# power_node.net
KiCad netlist of a schematic drawn in EAGLE
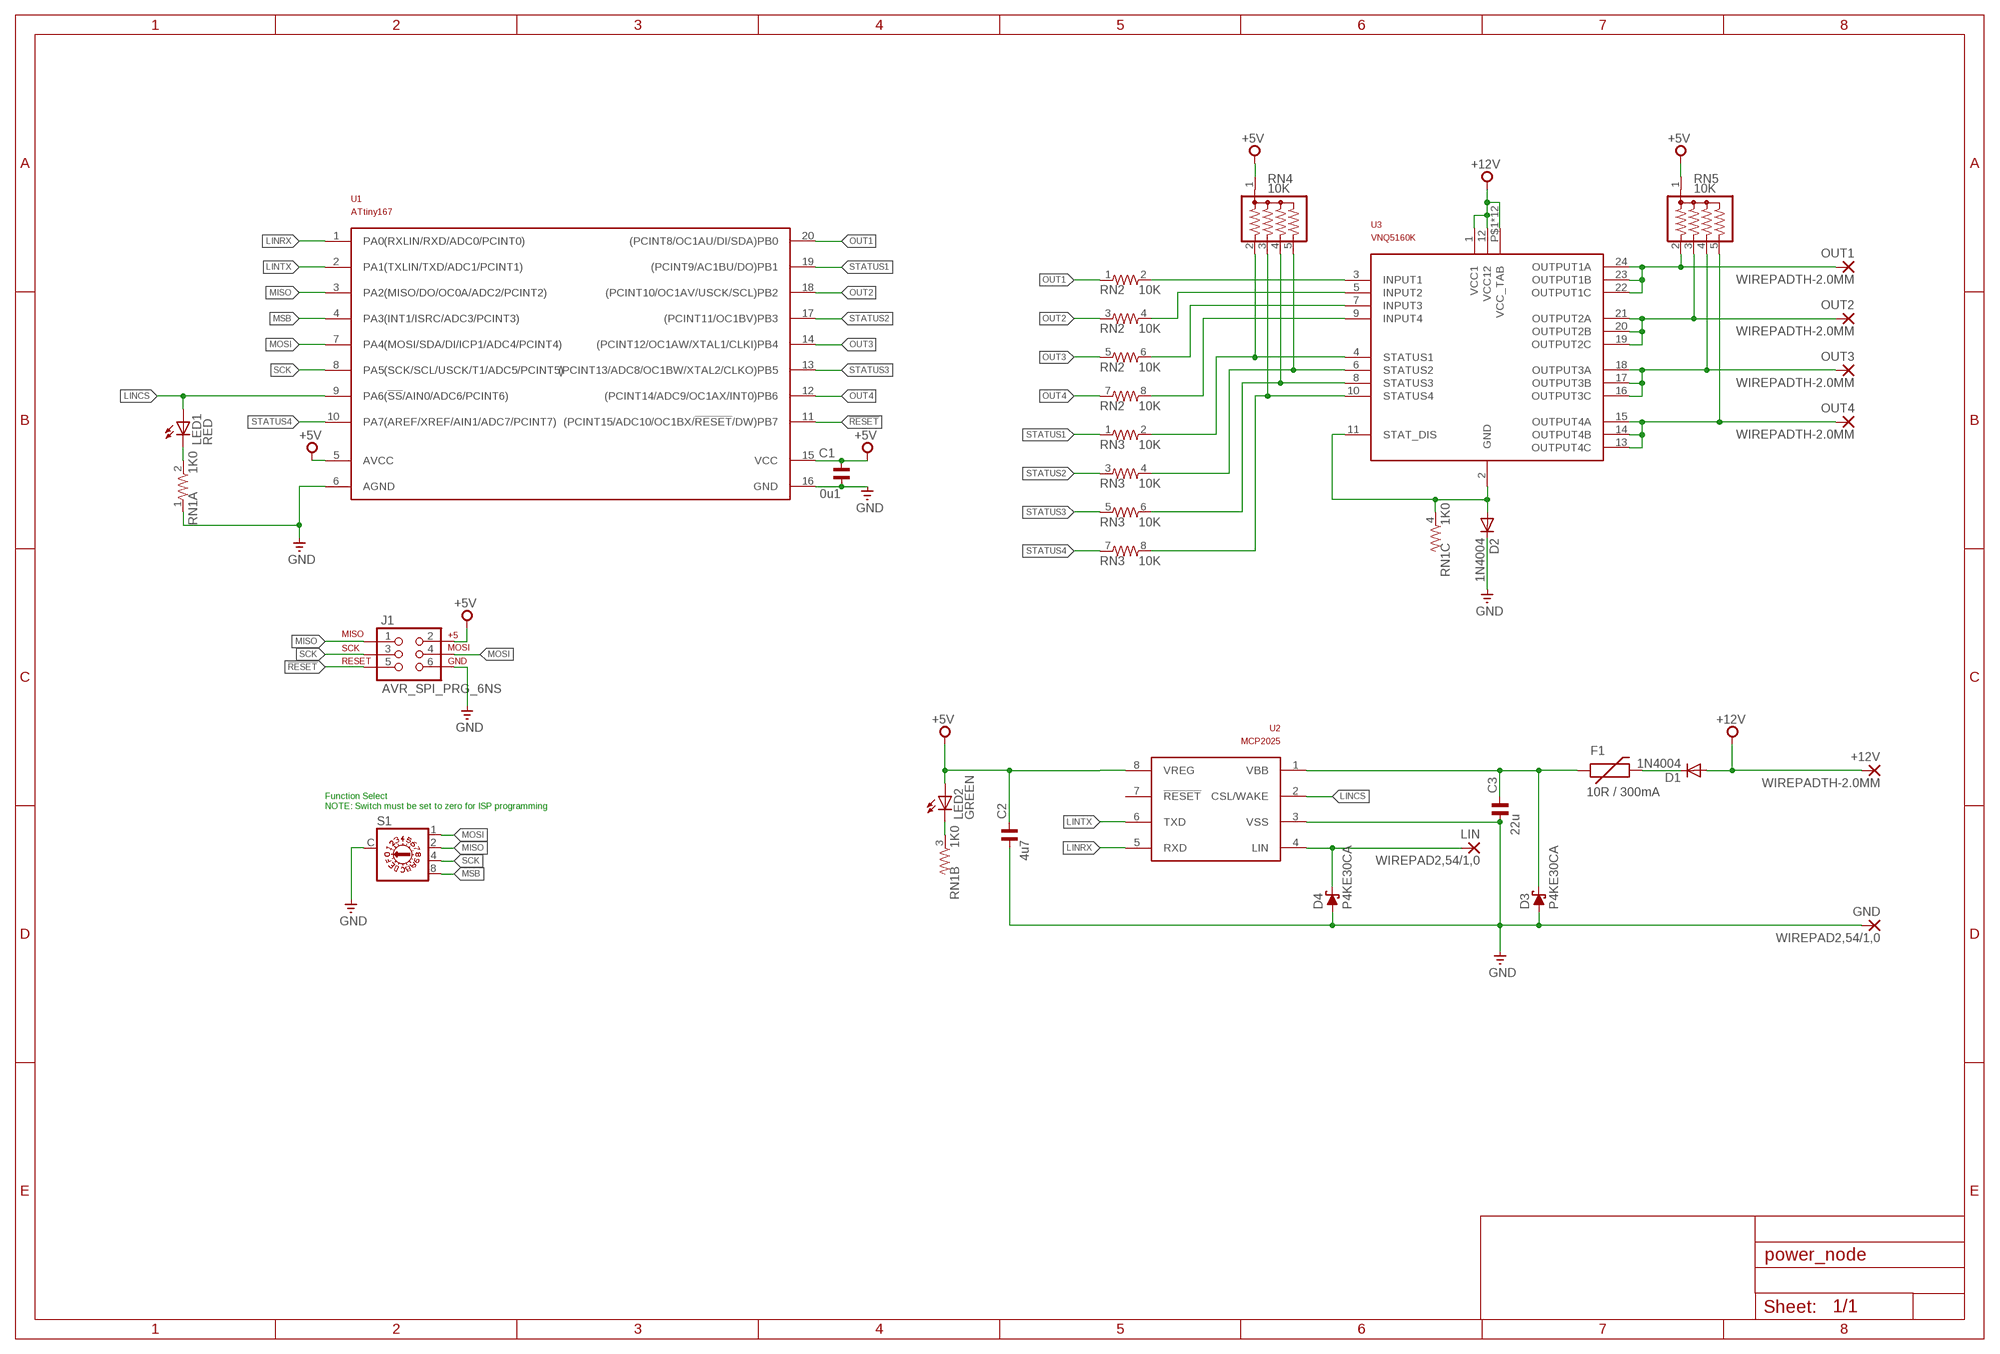
[diagram p0: schematic, sheet 1]

(export (version "E")
  (design (tool "Eeschema 10.0.6"))
  (components
    (comp (ref "+12V")
      (value "WIREPADTH-2.0MM")
      (footprint "eagle-import:WIREPAD-TH-2.0MM")
      (libsource (lib "eagle-import") (part "WIREPADTH-2.0MM"))
    )
    (comp (ref "C1")
      (value "0u1")
      (footprint "eagle-import:C025-024X044")
      (fields (field (name "PARTNO") "FK28X7R1H104K"))
      (libsource (lib "eagle-import") (part "C-EU025-024X044"))
    )
    (comp (ref "C2")
      (value "4u7")
      (footprint "eagle-import:C050-024X044")
      (fields (field (name "PARTNO") "FK28X5R0J475K"))
      (libsource (lib "eagle-import") (part "C-EU050-024X044"))
    )
    (comp (ref "C3")
      (value "22u")
      (footprint "eagle-import:C050-024X044")
      (fields (field (name "PARTNO") "FK22X5R1E226M"))
      (libsource (lib "eagle-import") (part "C-EU050-024X044"))
    )
    (comp (ref "D1")
      (value "1N4004")
      (footprint "eagle-import:DO41-10")
      (fields (field (name "PARTNO") "1N4004-TP"))
      (libsource (lib "eagle-import") (part "1N4004"))
    )
    (comp (ref "D2")
      (value "1N4004")
      (footprint "eagle-import:DO41-10")
      (fields (field (name "PARTNO") "1N4004-TP"))
      (libsource (lib "eagle-import") (part "1N4004"))
    )
    (comp (ref "D3")
      (value "P4KE30CA")
      (footprint "eagle-import:DO41-10")
      (libsource (lib "eagle-import") (part "P4KEXX"))
    )
    (comp (ref "D4")
      (value "P4KE30CA")
      (footprint "eagle-import:DO41-10")
      (libsource (lib "eagle-import") (part "P4KEXX"))
    )
    (comp (ref "F1")
      (value "10R / 300mA")
      (footprint "eagle-import:PTC")
      (fields (field (name "PARTNO") "600R150-RBZR"))
      (libsource (lib "eagle-import") (part "PTCPTH"))
    )
    (comp (ref "GND")
      (value "WIREPAD2,54/1,0")
      (footprint "eagle-import:2,54_1,0")
      (libsource (lib "eagle-import") (part "WIREPAD2,54/1,0"))
    )
    (comp (ref "J1")
      (value "AVR_SPI_PRG_6NS")
      (footprint "eagle-import:2X3-NS")
      (libsource (lib "eagle-import") (part "AVR_SPI_PRG_6NS"))
    )
    (comp (ref "LED1")
      (value "RED")
      (footprint "eagle-import:LED3MM")
      (fields (field (name "PARTNO") "C4SMF-RJS-CT0W0BB2"))
      (libsource (lib "eagle-import") (part "LED3MM"))
    )
    (comp (ref "LED2")
      (value "GREEN")
      (footprint "eagle-import:LED3MM")
      (fields (field (name "PARTNO") "C4SMF-GJS-CV0Y0792"))
      (libsource (lib "eagle-import") (part "LED3MM"))
    )
    (comp (ref "LIN")
      (value "WIREPAD2,54/1,0")
      (footprint "eagle-import:2,54_1,0")
      (libsource (lib "eagle-import") (part "WIREPAD2,54/1,0"))
    )
    (comp (ref "OUT1")
      (value "WIREPADTH-2.0MM")
      (footprint "eagle-import:WIREPAD-TH-2.0MM")
      (libsource (lib "eagle-import") (part "WIREPADTH-2.0MM"))
    )
    (comp (ref "OUT2")
      (value "WIREPADTH-2.0MM")
      (footprint "eagle-import:WIREPAD-TH-2.0MM")
      (libsource (lib "eagle-import") (part "WIREPADTH-2.0MM"))
    )
    (comp (ref "OUT3")
      (value "WIREPADTH-2.0MM")
      (footprint "eagle-import:WIREPAD-TH-2.0MM")
      (libsource (lib "eagle-import") (part "WIREPADTH-2.0MM"))
    )
    (comp (ref "OUT4")
      (value "WIREPADTH-2.0MM")
      (footprint "eagle-import:WIREPAD-TH-2.0MM")
      (libsource (lib "eagle-import") (part "WIREPADTH-2.0MM"))
    )
    (comp (ref "RN1")
      (value "1K0")
      (footprint "eagle-import:SIL4")
      (fields (field (name "PARTNO") "4604X-101-103LF"))
      (libsource (lib "eagle-import") (part "GE03R"))
    )
    (comp (ref "RN2")
      (value "10K")
      (footprint "eagle-import:SIL8")
      (fields (field (name "PARTNO") "4608X-102-103LF"))
      (libsource (lib "eagle-import") (part "E4RP"))
    )
    (comp (ref "RN3")
      (value "10K")
      (footprint "eagle-import:SIL8")
      (fields (field (name "PARTNO") "4608X-102-103LF"))
      (libsource (lib "eagle-import") (part "E4RP"))
    )
    (comp (ref "RN4")
      (value "10K")
      (footprint "eagle-import:SIL5")
      (fields (field (name "PARTNO") "4605X-101-103LF"))
      (libsource (lib "eagle-import") (part "G04R"))
    )
    (comp (ref "RN5")
      (value "10K")
      (footprint "eagle-import:SIL5")
      (fields (field (name "PARTNO") "4605X-101-103LF"))
      (libsource (lib "eagle-import") (part "G04R"))
    )
    (comp (ref "S1")
      (value "P103")
      (footprint "eagle-import:P103")
      (fields (field (name "PARTNO") "SH-7050MC"))
      (libsource (lib "eagle-import") (part "P103"))
    )
    (comp (ref "U1")
      (value "ATtiny167")
      (footprint "eagle-import:SO20W")
      (fields (field (name "PARTNO") "ATTINY167-SU"))
      (libsource (lib "eagle-import") (part "ATTINY167"))
    )
    (comp (ref "U2")
      (value "MCP2025")
      (footprint "eagle-import:SO08")
      (fields (field (name "PARTNO") "MCP2025-500E/SN"))
      (libsource (lib "eagle-import") (part "MCP2025"))
    )
    (comp (ref "U3")
      (value "VNQ5160K")
      (footprint "eagle-import:POWERSSO24")
      (fields (field (name "PARTNO") "VNQ5E160KTR-E"))
      (libsource (lib "eagle-import") (part "VNQ5160K"))
    )
  )
  (nets
    (net (code "1") (name "+5V") (class "Default")
      (node (ref "C1") (pin "1") (pinfunction "1_1") (pintype "passive"))
      (node (ref "C2") (pin "1") (pinfunction "1_1") (pintype "passive"))
      (node (ref "J1") (pin "2") (pinfunction "2_2") (pintype "passive"))
      (node (ref "LED2") (pin "A") (pinfunction "A_A") (pintype "passive"))
      (node (ref "RN4") (pin "1") (pinfunction "1_1") (pintype "passive"))
      (node (ref "RN5") (pin "1") (pinfunction "1_1") (pintype "passive"))
      (node (ref "U1") (pin "15") (pinfunction "VCC_15") (pintype "power_in"))
      (node (ref "U1") (pin "5") (pinfunction "AVCC_5") (pintype "power_in"))
      (node (ref "U2") (pin "8") (pinfunction "VREG_8") (pintype "power_in"))
    )
    (net (code "2") (name "+12V") (class "Default")
      (node (ref "+12V") (pin "1") (pinfunction "P_1") (pintype "passive"))
      (node (ref "D1") (pin "A") (pinfunction "A_A") (pintype "passive"))
      (node (ref "U3") (pin "1") (pinfunction "VCC1_1") (pintype "power_in"))
      (node (ref "U3") (pin "12") (pinfunction "VCC12_12") (pintype "power_in"))
      (node (ref "U3") (pin "P$1") (pinfunction "VCC_TAB_P$1") (pintype "power_in"))
      (node (ref "U3") (pin "P$10") (pinfunction "VCC_TAB_P$10") (pintype "power_in"))
      (node (ref "U3") (pin "P$11") (pinfunction "VCC_TAB_P$11") (pintype "power_in"))
      (node (ref "U3") (pin "P$12") (pinfunction "VCC_TAB_P$12") (pintype "power_in"))
      (node (ref "U3") (pin "P$2") (pinfunction "VCC_TAB_P$2") (pintype "power_in"))
      (node (ref "U3") (pin "P$3") (pinfunction "VCC_TAB_P$3") (pintype "power_in"))
      (node (ref "U3") (pin "P$4") (pinfunction "VCC_TAB_P$4") (pintype "power_in"))
      (node (ref "U3") (pin "P$5") (pinfunction "VCC_TAB_P$5") (pintype "power_in"))
      (node (ref "U3") (pin "P$6") (pinfunction "VCC_TAB_P$6") (pintype "power_in"))
      (node (ref "U3") (pin "P$7") (pinfunction "VCC_TAB_P$7") (pintype "power_in"))
      (node (ref "U3") (pin "P$8") (pinfunction "VCC_TAB_P$8") (pintype "power_in"))
      (node (ref "U3") (pin "P$9") (pinfunction "VCC_TAB_P$9") (pintype "power_in"))
    )
    (net (code "3") (name "/~{RESET}") (class "Default")
      (node (ref "J1") (pin "5") (pinfunction "5_5") (pintype "passive"))
      (node (ref "U1") (pin "11") (pinfunction "(PCINT15/ADC10/OC1BX/~{RESET}/DW)PB7_11") (pintype "bidirectional"))
    )
    (net (code "4") (name "GND") (class "Default")
      (node (ref "C1") (pin "2") (pinfunction "2_2") (pintype "passive"))
      (node (ref "C2") (pin "2") (pinfunction "2_2") (pintype "passive"))
      (node (ref "C3") (pin "2") (pinfunction "2_2") (pintype "passive"))
      (node (ref "D2") (pin "C") (pinfunction "C_C") (pintype "passive"))
      (node (ref "D3") (pin "A") (pinfunction "A_A") (pintype "passive"))
      (node (ref "D4") (pin "A") (pinfunction "A_A") (pintype "passive"))
      (node (ref "GND") (pin "1") (pinfunction "P_1") (pintype "passive"))
      (node (ref "J1") (pin "6") (pinfunction "6_6") (pintype "passive"))
      (node (ref "RN1") (pin "1") (pinfunction "1_1") (pintype "passive"))
      (node (ref "S1") (pin "C") (pinfunction "C_C") (pintype "passive"))
      (node (ref "U1") (pin "16") (pinfunction "GND_16") (pintype "power_in"))
      (node (ref "U1") (pin "6") (pinfunction "AGND_6") (pintype "power_in"))
      (node (ref "U2") (pin "3") (pinfunction "VSS_3") (pintype "power_in"))
    )
    (net (code "5") (name "LINCS") (class "Default")
      (node (ref "LED1") (pin "A") (pinfunction "A_A") (pintype "passive"))
      (node (ref "U1") (pin "9") (pinfunction "PA6(~{SS}/AIN0/ADC6/PCINT6)_9") (pintype "bidirectional"))
      (node (ref "U2") (pin "2") (pinfunction "CSL/WAKE_2") (pintype "input"))
    )
    (net (code "6") (name "LINRX") (class "Default")
      (node (ref "U1") (pin "1") (pinfunction "PA0(RXLIN/RXD/ADC0/PCINT0)_1") (pintype "bidirectional"))
      (node (ref "U2") (pin "5") (pinfunction "RXD_5") (pintype "output"))
    )
    (net (code "7") (name "LINTX") (class "Default")
      (node (ref "U1") (pin "2") (pinfunction "PA1(TXLIN/TXD/ADC1/PCINT1)_2") (pintype "bidirectional"))
      (node (ref "U2") (pin "6") (pinfunction "TXD_6") (pintype "input"))
    )
    (net (code "8") (name "MISO") (class "Default")
      (node (ref "J1") (pin "1") (pinfunction "1_1") (pintype "passive"))
      (node (ref "S1") (pin "2") (pinfunction "2_2") (pintype "passive"))
      (node (ref "U1") (pin "3") (pinfunction "PA2(MISO/DO/OC0A/ADC2/PCINT2)_3") (pintype "bidirectional"))
    )
    (net (code "9") (name "MOSI") (class "Default")
      (node (ref "J1") (pin "4") (pinfunction "4_4") (pintype "passive"))
      (node (ref "S1") (pin "1") (pinfunction "1_1") (pintype "passive"))
      (node (ref "U1") (pin "7") (pinfunction "PA4(MOSI/SDA/DI/ICP1/ADC4/PCINT4)_7") (pintype "bidirectional"))
    )
    (net (code "10") (name "MSB") (class "Default")
      (node (ref "S1") (pin "8") (pinfunction "8_8") (pintype "passive"))
      (node (ref "U1") (pin "4") (pinfunction "PA3(INT1/ISRC/ADC3/PCINT3)_4") (pintype "bidirectional"))
    )
    (net (code "11") (name "Net-(F1-1)") (class "Default")
      (node (ref "C3") (pin "1") (pinfunction "1_1") (pintype "passive"))
      (node (ref "D3") (pin "C") (pinfunction "C_C") (pintype "passive"))
      (node (ref "F1") (pin "P$1") (pinfunction "1_P$1") (pintype "bidirectional"))
      (node (ref "U2") (pin "1") (pinfunction "VBB_1") (pintype "power_in"))
    )
    (net (code "12") (name "Net-(F1-2)") (class "Default")
      (node (ref "D1") (pin "C") (pinfunction "C_C") (pintype "passive"))
      (node (ref "F1") (pin "P$2") (pinfunction "2_P$2") (pintype "bidirectional"))
    )
    (net (code "13") (name "Net-(LED1-C)") (class "Default")
      (node (ref "LED1") (pin "K") (pinfunction "C_K") (pintype "passive"))
      (node (ref "RN1") (pin "2") (pinfunction "2_2") (pintype "passive"))
    )
    (net (code "14") (name "Net-(LED2-C)") (class "Default")
      (node (ref "LED2") (pin "K") (pinfunction "C_K") (pintype "passive"))
      (node (ref "RN1") (pin "3") (pinfunction "2_3") (pintype "passive"))
    )
    (net (code "15") (name "Net-(LIN-P)") (class "Default")
      (node (ref "D4") (pin "C") (pinfunction "C_C") (pintype "passive"))
      (node (ref "LIN") (pin "1") (pinfunction "P_1") (pintype "passive"))
      (node (ref "U2") (pin "4") (pinfunction "LIN_4") (pintype "bidirectional"))
    )
    (net (code "16") (name "Net-(OUT1-P)") (class "Default")
      (node (ref "OUT1") (pin "1") (pinfunction "P_1") (pintype "passive"))
      (node (ref "RN5") (pin "2") (pinfunction "2_2") (pintype "passive"))
      (node (ref "U3") (pin "22") (pinfunction "OUTPUT1C_22") (pintype "output"))
      (node (ref "U3") (pin "23") (pinfunction "OUTPUT1B_23") (pintype "output"))
      (node (ref "U3") (pin "24") (pinfunction "OUTPUT1A_24") (pintype "output"))
    )
    (net (code "17") (name "Net-(OUT2-P)") (class "Default")
      (node (ref "OUT2") (pin "1") (pinfunction "P_1") (pintype "passive"))
      (node (ref "RN5") (pin "3") (pinfunction "3_3") (pintype "passive"))
      (node (ref "U3") (pin "19") (pinfunction "OUTPUT2C_19") (pintype "output"))
      (node (ref "U3") (pin "20") (pinfunction "OUTPUT2B_20") (pintype "output"))
      (node (ref "U3") (pin "21") (pinfunction "OUTPUT2A_21") (pintype "output"))
    )
    (net (code "18") (name "Net-(OUT3-P)") (class "Default")
      (node (ref "OUT3") (pin "1") (pinfunction "P_1") (pintype "passive"))
      (node (ref "RN5") (pin "4") (pinfunction "4_4") (pintype "passive"))
      (node (ref "U3") (pin "16") (pinfunction "OUTPUT3C_16") (pintype "output"))
      (node (ref "U3") (pin "17") (pinfunction "OUTPUT3B_17") (pintype "output"))
      (node (ref "U3") (pin "18") (pinfunction "OUTPUT3A_18") (pintype "output"))
    )
    (net (code "19") (name "Net-(OUT4-P)") (class "Default")
      (node (ref "OUT4") (pin "1") (pinfunction "P_1") (pintype "passive"))
      (node (ref "RN5") (pin "5") (pinfunction "5_5") (pintype "passive"))
      (node (ref "U3") (pin "13") (pinfunction "OUTPUT4C_13") (pintype "output"))
      (node (ref "U3") (pin "14") (pinfunction "OUTPUT4B_14") (pintype "output"))
      (node (ref "U3") (pin "15") (pinfunction "OUTPUT4A_15") (pintype "output"))
    )
    (net (code "20") (name "Net-(RN1C-2)") (class "Default")
      (node (ref "D2") (pin "A") (pinfunction "A_A") (pintype "passive"))
      (node (ref "RN1") (pin "4") (pinfunction "2_4") (pintype "passive"))
      (node (ref "U3") (pin "11") (pinfunction "STAT_DIS_11") (pintype "input"))
      (node (ref "U3") (pin "2") (pinfunction "GND_2") (pintype "power_in"))
    )
    (net (code "21") (name "Net-(RN2B-2)") (class "Default")
      (node (ref "RN2") (pin "4") (pinfunction "2_4") (pintype "passive"))
      (node (ref "U3") (pin "5") (pinfunction "INPUT2_5") (pintype "input"))
    )
    (net (code "22") (name "Net-(RN2C-2)") (class "Default")
      (node (ref "RN2") (pin "6") (pinfunction "2_6") (pintype "passive"))
      (node (ref "U3") (pin "7") (pinfunction "INPUT3_7") (pintype "input"))
    )
    (net (code "23") (name "Net-(RN2D-2)") (class "Default")
      (node (ref "RN2") (pin "8") (pinfunction "2_8") (pintype "passive"))
      (node (ref "U3") (pin "9") (pinfunction "INPUT4_9") (pintype "input"))
    )
    (net (code "24") (name "Net-(RN3B-2)") (class "Default")
      (node (ref "RN3") (pin "4") (pinfunction "2_4") (pintype "passive"))
      (node (ref "RN4") (pin "5") (pinfunction "5_5") (pintype "passive"))
      (node (ref "U3") (pin "6") (pinfunction "STATUS2_6") (pintype "output"))
    )
    (net (code "25") (name "Net-(RN3C-2)") (class "Default")
      (node (ref "RN3") (pin "6") (pinfunction "2_6") (pintype "passive"))
      (node (ref "RN4") (pin "4") (pinfunction "4_4") (pintype "passive"))
      (node (ref "U3") (pin "8") (pinfunction "STATUS3_8") (pintype "output"))
    )
    (net (code "26") (name "Net-(RN3D-2)") (class "Default")
      (node (ref "RN3") (pin "8") (pinfunction "2_8") (pintype "passive"))
      (node (ref "RN4") (pin "3") (pinfunction "3_3") (pintype "passive"))
      (node (ref "U3") (pin "10") (pinfunction "STATUS4_10") (pintype "output"))
    )
    (net (code "27") (name "Net-(U3-INPUT1)") (class "Default")
      (node (ref "RN2") (pin "2") (pinfunction "2_2") (pintype "passive"))
      (node (ref "U3") (pin "3") (pinfunction "INPUT1_3") (pintype "input"))
    )
    (net (code "28") (name "Net-(U3-STATUS1)") (class "Default")
      (node (ref "RN3") (pin "2") (pinfunction "2_2") (pintype "passive"))
      (node (ref "RN4") (pin "2") (pinfunction "2_2") (pintype "passive"))
      (node (ref "U3") (pin "4") (pinfunction "STATUS1_4") (pintype "output"))
    )
    (net (code "29") (name "OUT1") (class "Default")
      (node (ref "RN2") (pin "1") (pinfunction "1_1") (pintype "passive"))
      (node (ref "U1") (pin "20") (pinfunction "(PCINT8/OC1AU/DI/SDA)PB0_20") (pintype "bidirectional"))
    )
    (net (code "30") (name "OUT2") (class "Default")
      (node (ref "RN2") (pin "3") (pinfunction "1_3") (pintype "passive"))
      (node (ref "U1") (pin "18") (pinfunction "(PCINT10/OC1AV/USCK/SCL)PB2_18") (pintype "bidirectional"))
    )
    (net (code "31") (name "OUT3") (class "Default")
      (node (ref "RN2") (pin "5") (pinfunction "1_5") (pintype "passive"))
      (node (ref "U1") (pin "14") (pinfunction "(PCINT12/OC1AW/XTAL1/CLKI)PB4_14") (pintype "bidirectional"))
    )
    (net (code "32") (name "OUT4") (class "Default")
      (node (ref "RN2") (pin "7") (pinfunction "1_7") (pintype "passive"))
      (node (ref "U1") (pin "12") (pinfunction "(PCINT14/ADC9/OC1AX/INT0)PB6_12") (pintype "bidirectional"))
    )
    (net (code "33") (name "SCK") (class "Default")
      (node (ref "J1") (pin "3") (pinfunction "3_3") (pintype "passive"))
      (node (ref "S1") (pin "4") (pinfunction "4_4") (pintype "passive"))
      (node (ref "U1") (pin "8") (pinfunction "PA5(SCK/SCL/USCK/T1/ADC5/PCINT5)_8") (pintype "bidirectional"))
    )
    (net (code "34") (name "STATUS1") (class "Default")
      (node (ref "RN3") (pin "1") (pinfunction "1_1") (pintype "passive"))
      (node (ref "U1") (pin "19") (pinfunction "(PCINT9/AC1BU/DO)PB1_19") (pintype "bidirectional"))
    )
    (net (code "35") (name "STATUS2") (class "Default")
      (node (ref "RN3") (pin "3") (pinfunction "1_3") (pintype "passive"))
      (node (ref "U1") (pin "17") (pinfunction "(PCINT11/OC1BV)PB3_17") (pintype "bidirectional"))
    )
    (net (code "36") (name "STATUS3") (class "Default")
      (node (ref "RN3") (pin "5") (pinfunction "1_5") (pintype "passive"))
      (node (ref "U1") (pin "13") (pinfunction "(PCINT13/ADC8/OC1BW/XTAL2/CLKO)PB5_13") (pintype "bidirectional"))
    )
    (net (code "37") (name "STATUS4") (class "Default")
      (node (ref "RN3") (pin "7") (pinfunction "1_7") (pintype "passive"))
      (node (ref "U1") (pin "10") (pinfunction "PA7(AREF/XREF/AIN1/ADC7/PCINT7)_10") (pintype "bidirectional"))
    )
    (net (code "38") (name "unconnected-(U2-~{RESET}-Pad7)") (class "Default")
      (node (ref "U2") (pin "7") (pinfunction "~{RESET}_7") (pintype "open_collector"))
    )
  )
)
